# schema.net
KiCad netlist of a schematic drawn in EAGLE
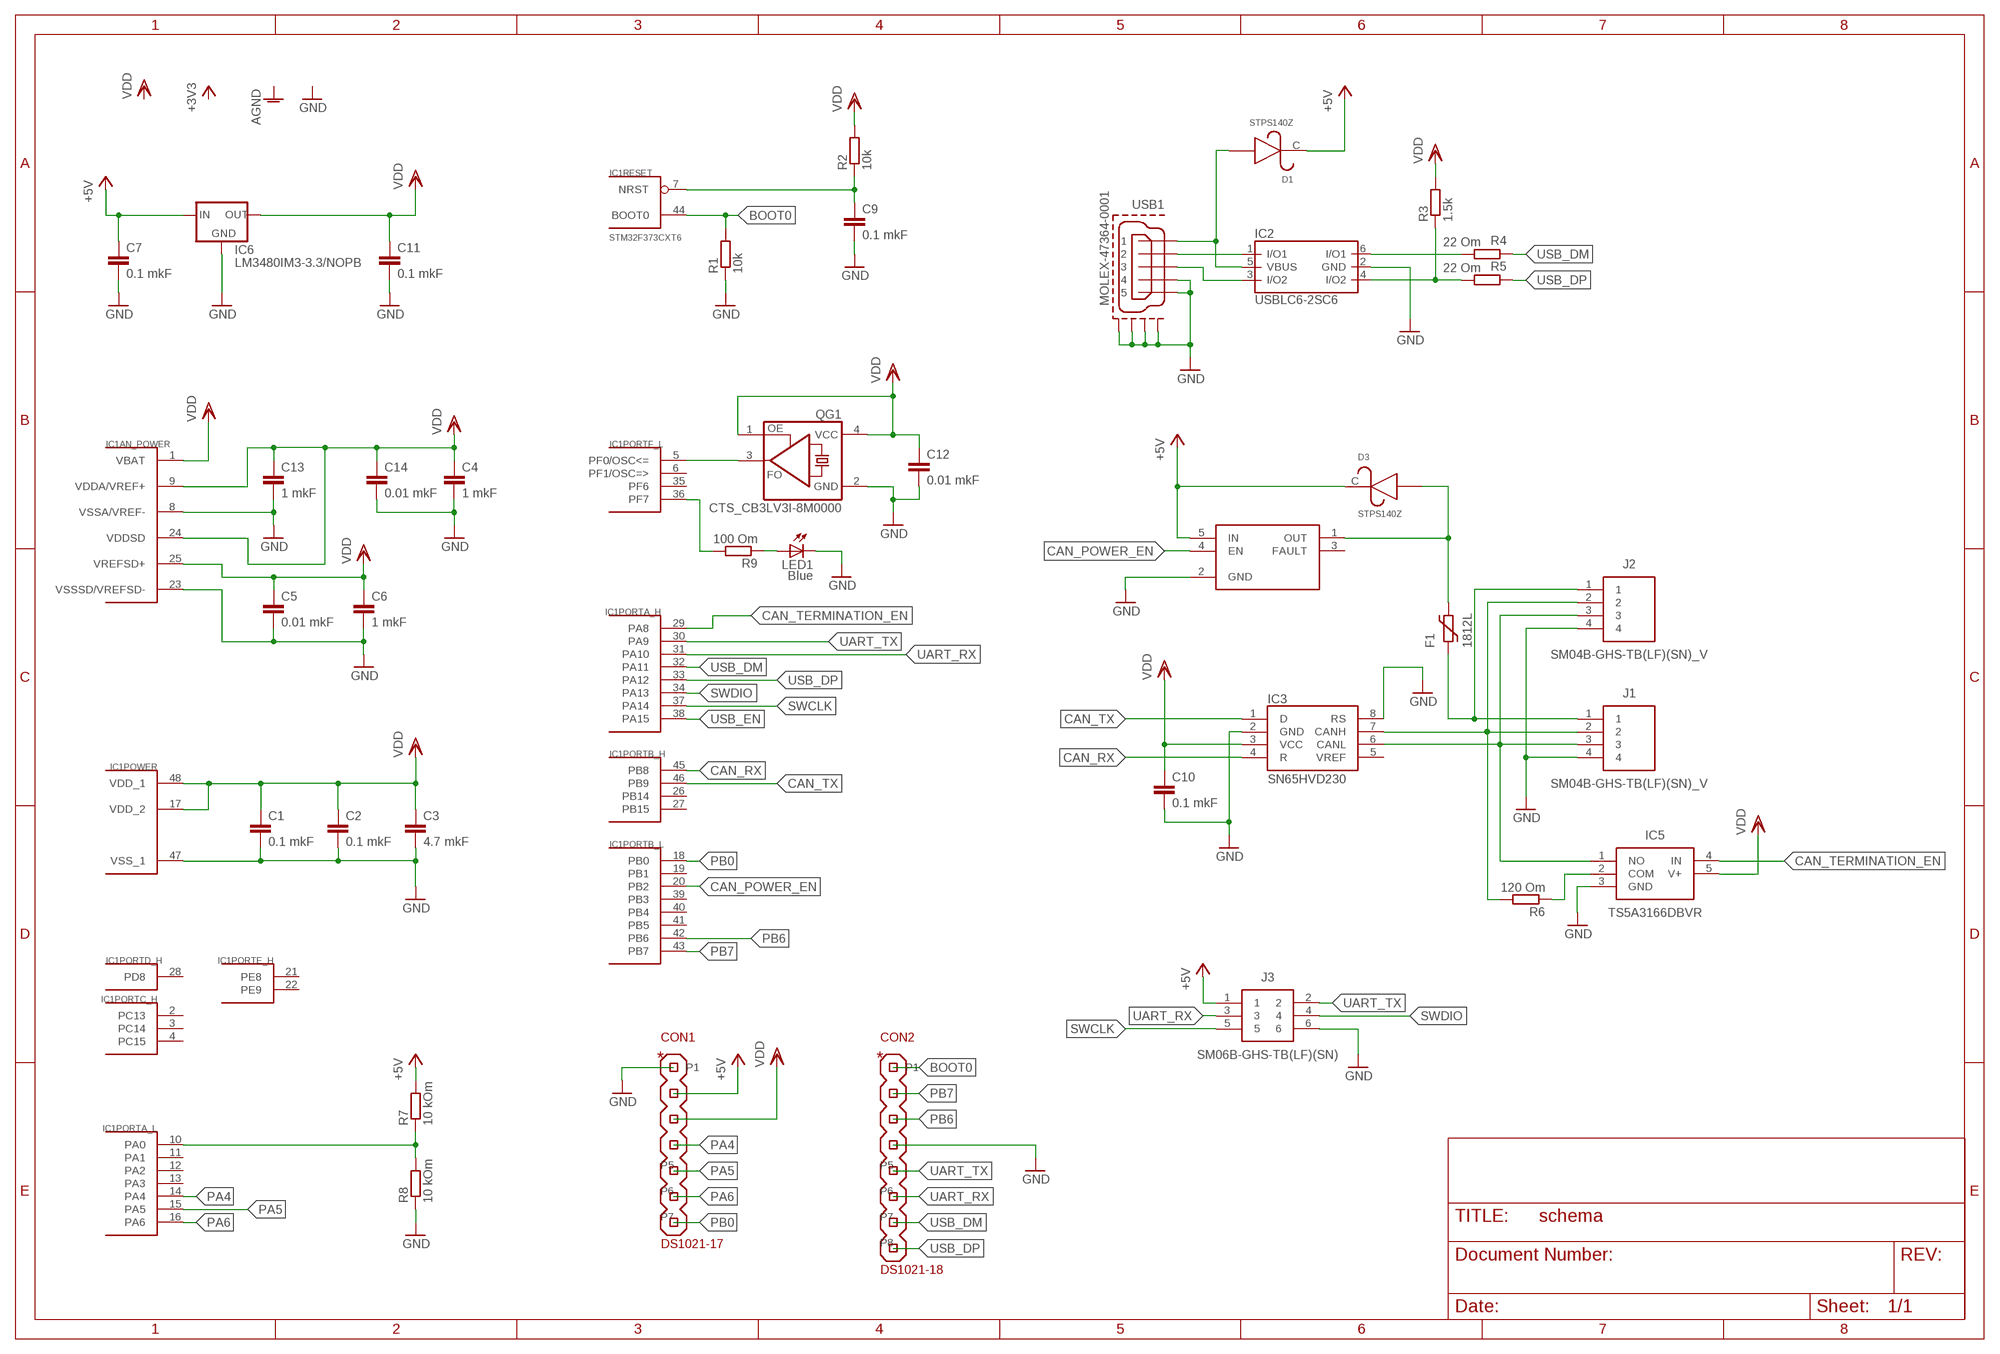
[diagram p0: schematic, sheet 1]

(export (version "E")
  (design (tool "Eeschema 10.0.6"))
  (components
    (comp (ref "C1")
      (value "0.1 mkF")
      (footprint "eagle-import:C0603")
      (libsource (lib "eagle-import") (part "C-EUC0603"))
    )
    (comp (ref "C2")
      (value "0.1 mkF")
      (footprint "eagle-import:C0603")
      (libsource (lib "eagle-import") (part "C-EUC0603"))
    )
    (comp (ref "C3")
      (value "4.7 mkF")
      (footprint "eagle-import:C0805")
      (libsource (lib "eagle-import") (part "C-EUC0805"))
    )
    (comp (ref "C4")
      (value "1 mkF")
      (footprint "eagle-import:C0603")
      (libsource (lib "eagle-import") (part "C-EUC0603"))
    )
    (comp (ref "C5")
      (value "0.01 mkF")
      (footprint "eagle-import:C0603")
      (libsource (lib "eagle-import") (part "C-EUC0603"))
    )
    (comp (ref "C6")
      (value "1 mkF")
      (footprint "eagle-import:C0603")
      (libsource (lib "eagle-import") (part "C-EUC0603"))
    )
    (comp (ref "C7")
      (value "0.1 mkF")
      (footprint "eagle-import:C0603")
      (libsource (lib "eagle-import") (part "C-EUC0603"))
    )
    (comp (ref "C9")
      (value "0.1 mkF")
      (footprint "eagle-import:C0603")
      (libsource (lib "eagle-import") (part "C-EUC0603"))
    )
    (comp (ref "C10")
      (value "0.1 mkF")
      (footprint "eagle-import:C0603")
      (libsource (lib "eagle-import") (part "C-EUC0603"))
    )
    (comp (ref "C11")
      (value "0.1 mkF")
      (footprint "eagle-import:C0603")
      (libsource (lib "eagle-import") (part "C-EUC0603"))
    )
    (comp (ref "C12")
      (value "0.01 mkF")
      (footprint "eagle-import:C0603")
      (libsource (lib "eagle-import") (part "C-EUC0603"))
    )
    (comp (ref "C13")
      (value "1 mkF")
      (footprint "eagle-import:C0603")
      (libsource (lib "eagle-import") (part "C-EUC0603"))
    )
    (comp (ref "C14")
      (value "0.01 mkF")
      (footprint "eagle-import:C0603")
      (libsource (lib "eagle-import") (part "C-EUC0603"))
    )
    (comp (ref "CON1")
      (value "DS1021-17")
      (footprint "eagle-import:DS1021-1_7")
      (libsource (lib "eagle-import") (part "DS1021-17"))
    )
    (comp (ref "CON2")
      (value "DS1021-18")
      (footprint "eagle-import:DS1021-1_8")
      (libsource (lib "eagle-import") (part "DS1021-18"))
    )
    (comp (ref "D1")
      (value "STPS140Z")
      (footprint "eagle-import:SOD123")
      (libsource (lib "eagle-import") (part "STPS140Z"))
    )
    (comp (ref "D3")
      (value "STPS140Z")
      (footprint "eagle-import:SOD123")
      (libsource (lib "eagle-import") (part "STPS140Z"))
    )
    (comp (ref "F1")
      (value "1812L")
      (footprint "eagle-import:1812L")
      (libsource (lib "eagle-import") (part "1812L"))
    )
    (comp (ref "IC1")
      (value "STM32F373CXT6")
      (footprint "eagle-import:TQFP48")
      (libsource (lib "eagle-import") (part "STM32F373CXT6"))
    )
    (comp (ref "IC2")
      (value "USBLC6-2SC6")
      (footprint "eagle-import:SOT23-6L")
      (libsource (lib "eagle-import") (part "USBLC6-2SC6"))
    )
    (comp (ref "IC3")
      (value "SN65HVD230")
      (footprint "eagle-import:SO8")
      (libsource (lib "eagle-import") (part "SN65HVD230"))
    )
    (comp (ref "IC5")
      (value "TS5A3166DBVR")
      (footprint "eagle-import:SOT23-5")
      (libsource (lib "eagle-import") (part "TS5A3166DBVR"))
    )
    (comp (ref "IC6")
      (value "LM3480IM3-3.3/NOPB")
      (footprint "eagle-import:SOT23")
      (libsource (lib "eagle-import") (part "LM3480IM3-3.3/NOPB"))
    )
    (comp (ref "IC7")
      (value "STMPS2171STR")
      (footprint "eagle-import:SOT23-5L")
      (libsource (lib "eagle-import") (part "STMPS2171STR"))
    )
    (comp (ref "J1")
      (value "SM04B-GHS-TB(LF)(SN)_V")
      (footprint "eagle-import:SM04B-GHS-TB")
      (fields
        (field (name "MANUFACTURER_PART_NUMBER") "SM04B-GHS-TB(LF)(SN)")
        (field (name "RS_PART_NUMBER") "7521797")
      )
      (libsource (lib "eagle-import") (part "SM04B-GHS-TB(LF)(SN)_V"))
    )
    (comp (ref "J2")
      (value "SM04B-GHS-TB(LF)(SN)_V")
      (footprint "eagle-import:SM04B-GHS-TB")
      (fields
        (field (name "MANUFACTURER_PART_NUMBER") "SM04B-GHS-TB(LF)(SN)")
        (field (name "RS_PART_NUMBER") "7521797")
      )
      (libsource (lib "eagle-import") (part "SM04B-GHS-TB(LF)(SN)_V"))
    )
    (comp (ref "J3")
      (value "SM06B-GHS-TB(LF)(SN)")
      (footprint "eagle-import:SM06B-GHS-TB")
      (fields (field (name "RS_PART_NUMBER") "7521800"))
      (libsource (lib "eagle-import") (part "SM06B-GHS-TB(LF)(SN)"))
    )
    (comp (ref "LED1")
      (value "Blue")
      (footprint "eagle-import:CHIPLED_0603")
      (libsource (lib "eagle-import") (part "LEDCHIPLED_0603"))
    )
    (comp (ref "QG1")
      (value "CTS_CB3LV3I-8M0000")
      (footprint "eagle-import:CTS_CB3")
      (libsource (lib "eagle-import") (part "CTS_CB3LV3I-8M0000"))
    )
    (comp (ref "R1")
      (value "10k")
      (footprint "eagle-import:R0603")
      (libsource (lib "eagle-import") (part "R-EU_R0603"))
    )
    (comp (ref "R2")
      (value "10k")
      (footprint "eagle-import:R0603")
      (libsource (lib "eagle-import") (part "R-EU_R0603"))
    )
    (comp (ref "R3")
      (value "1.5k")
      (footprint "eagle-import:R0603")
      (libsource (lib "eagle-import") (part "R-EU_R0603"))
    )
    (comp (ref "R4")
      (value "22 Om")
      (footprint "eagle-import:R0603")
      (libsource (lib "eagle-import") (part "R-EU_R0603"))
    )
    (comp (ref "R5")
      (value "22 Om")
      (footprint "eagle-import:R0603")
      (libsource (lib "eagle-import") (part "R-EU_R0603"))
    )
    (comp (ref "R6")
      (value "120 Om")
      (footprint "eagle-import:R1206")
      (libsource (lib "eagle-import") (part "R-EU_R1206"))
    )
    (comp (ref "R7")
      (value "10 kOm")
      (footprint "eagle-import:R0603")
      (libsource (lib "eagle-import") (part "R-EU_R0603"))
    )
    (comp (ref "R8")
      (value "10 kOm")
      (footprint "eagle-import:R0603")
      (libsource (lib "eagle-import") (part "R-EU_R0603"))
    )
    (comp (ref "R9")
      (value "100 Om")
      (footprint "eagle-import:R0603")
      (libsource (lib "eagle-import") (part "R-EU_R0603"))
    )
    (comp (ref "USB1")
      (value "MOLEX-47364-0001")
      (footprint "eagle-import:MOLEX-47364-0001")
      (libsource (lib "eagle-import") (part "MOLEX-47364-0001"))
    )
  )
  (nets
    (net (code "2") (name "+5V") (class "Default")
      (node (ref "C7") (pin "1") (pinfunction "1_1") (pintype "passive"))
      (node (ref "CON1") (pin "P2") (pinfunction "P2_P2") (pintype "bidirectional"))
      (node (ref "D1") (pin "C") (pinfunction "C_C") (pintype "power_in"))
      (node (ref "D3") (pin "C") (pinfunction "C_C") (pintype "power_in"))
      (node (ref "IC6") (pin "2") (pinfunction "IN_2") (pintype "input"))
      (node (ref "IC7") (pin "5") (pinfunction "IN_5") (pintype "power_in"))
      (node (ref "J3") (pin "1") (pinfunction "1_1") (pintype "passive"))
      (node (ref "R7") (pin "2") (pinfunction "2_2") (pintype "passive"))
    )
    (net (code "4") (name "BOOT0") (class "Default")
      (node (ref "CON2") (pin "P1") (pinfunction "P1_P1") (pintype "bidirectional"))
      (node (ref "IC1") (pin "44") (pinfunction "BOOT0_44") (pintype "input"))
      (node (ref "R1") (pin "2") (pinfunction "2_2") (pintype "passive"))
    )
    (net (code "5") (name "CAN_POWER_EN") (class "Default")
      (node (ref "IC1") (pin "20") (pinfunction "PB2_20") (pintype "bidirectional"))
      (node (ref "IC7") (pin "4") (pinfunction "EN_4") (pintype "bidirectional"))
    )
    (net (code "6") (name "CAN_RX") (class "Default")
      (node (ref "IC1") (pin "45") (pinfunction "PB8_45") (pintype "bidirectional"))
      (node (ref "IC3") (pin "4") (pinfunction "R_4") (pintype "bidirectional"))
    )
    (net (code "7") (name "CAN_TERMINATION_EN") (class "Default")
      (node (ref "IC1") (pin "29") (pinfunction "PA8_29") (pintype "bidirectional"))
      (node (ref "IC5") (pin "4") (pinfunction "IN_4") (pintype "passive"))
    )
    (net (code "8") (name "CAN_TX") (class "Default")
      (node (ref "IC1") (pin "46") (pinfunction "PB9_46") (pintype "bidirectional"))
      (node (ref "IC3") (pin "1") (pinfunction "D_1") (pintype "bidirectional"))
    )
    (net (code "9") (name "GND") (class "Default")
      (node (ref "C1") (pin "2") (pinfunction "2_2") (pintype "passive"))
      (node (ref "C10") (pin "2") (pinfunction "2_2") (pintype "passive"))
      (node (ref "C11") (pin "2") (pinfunction "2_2") (pintype "passive"))
      (node (ref "C12") (pin "2") (pinfunction "2_2") (pintype "passive"))
      (node (ref "C13") (pin "2") (pinfunction "2_2") (pintype "passive"))
      (node (ref "C14") (pin "2") (pinfunction "2_2") (pintype "passive"))
      (node (ref "C2") (pin "2") (pinfunction "2_2") (pintype "passive"))
      (node (ref "C3") (pin "2") (pinfunction "2_2") (pintype "passive"))
      (node (ref "C4") (pin "2") (pinfunction "2_2") (pintype "passive"))
      (node (ref "C5") (pin "2") (pinfunction "2_2") (pintype "passive"))
      (node (ref "C6") (pin "2") (pinfunction "2_2") (pintype "passive"))
      (node (ref "C7") (pin "2") (pinfunction "2_2") (pintype "passive"))
      (node (ref "C9") (pin "2") (pinfunction "2_2") (pintype "passive"))
      (node (ref "CON1") (pin "P1") (pinfunction "P1_P1") (pintype "bidirectional"))
      (node (ref "CON2") (pin "P4") (pinfunction "P4_P4") (pintype "bidirectional"))
      (node (ref "IC1") (pin "23") (pinfunction "VSSSD/VREFSD-_23") (pintype "power_in"))
      (node (ref "IC1") (pin "47") (pinfunction "VSS_1_47") (pintype "power_in"))
      (node (ref "IC1") (pin "8") (pinfunction "VSSA/VREF-_8") (pintype "power_in"))
      (node (ref "IC2") (pin "2") (pinfunction "GND_2") (pintype "power_in"))
      (node (ref "IC3") (pin "2") (pinfunction "GND_2") (pintype "power_in"))
      (node (ref "IC3") (pin "8") (pinfunction "RS_8") (pintype "bidirectional"))
      (node (ref "IC5") (pin "3") (pinfunction "GND_3") (pintype "passive"))
      (node (ref "IC6") (pin "3") (pinfunction "GND_3") (pintype "input"))
      (node (ref "IC7") (pin "2") (pinfunction "GND_2") (pintype "power_in"))
      (node (ref "J1") (pin "4") (pinfunction "4_4") (pintype "passive"))
      (node (ref "J2") (pin "4") (pinfunction "4_4") (pintype "passive"))
      (node (ref "J3") (pin "6") (pinfunction "6_6") (pintype "passive"))
      (node (ref "LED1") (pin "C") (pinfunction "C_C") (pintype "passive"))
      (node (ref "QG1") (pin "2") (pinfunction "GND_2") (pintype "power_in"))
      (node (ref "R1") (pin "1") (pinfunction "1_1") (pintype "passive"))
      (node (ref "R8") (pin "1") (pinfunction "1_1") (pintype "passive"))
      (node (ref "USB1") (pin "4") (pinfunction "4_4") (pintype "input"))
      (node (ref "USB1") (pin "5") (pinfunction "5_5") (pintype "input"))
      (node (ref "USB1") (pin "GND1") (pinfunction "GND1_GND1") (pintype "bidirectional"))
      (node (ref "USB1") (pin "GND2") (pinfunction "GND2_GND2") (pintype "bidirectional"))
      (node (ref "USB1") (pin "GND3") (pinfunction "GND3_GND3") (pintype "bidirectional"))
      (node (ref "USB1") (pin "GND4") (pinfunction "GND4_GND4") (pintype "bidirectional"))
    )
    (net (code "10") (name "Net-(F1-Pad1)") (class "Default")
      (node (ref "F1") (pin "1") (pinfunction "1_1") (pintype "passive"))
      (node (ref "J1") (pin "1") (pinfunction "1_1") (pintype "passive"))
      (node (ref "J2") (pin "1") (pinfunction "1_1") (pintype "passive"))
    )
    (net (code "11") (name "Net-(IC1C-PA0)") (class "Default")
      (node (ref "IC1") (pin "10") (pinfunction "PA0_10") (pintype "bidirectional"))
      (node (ref "R7") (pin "1") (pinfunction "1_1") (pintype "passive"))
      (node (ref "R8") (pin "2") (pinfunction "2_2") (pintype "passive"))
    )
    (net (code "12") (name "Net-(IC1I-PF0{slash}OSC<=)") (class "Default")
      (node (ref "IC1") (pin "5") (pinfunction "PF0/OSC<=_5") (pintype "bidirectional"))
      (node (ref "QG1") (pin "3") (pinfunction "FO_3") (pintype "output"))
    )
    (net (code "13") (name "Net-(IC1I-PF7)") (class "Default")
      (node (ref "IC1") (pin "36") (pinfunction "PF7_36") (pintype "bidirectional"))
      (node (ref "R9") (pin "2") (pinfunction "2_2") (pintype "passive"))
    )
    (net (code "14") (name "Net-(IC1K-NRST)") (class "Default")
      (node (ref "C9") (pin "1") (pinfunction "1_1") (pintype "passive"))
      (node (ref "IC1") (pin "7") (pinfunction "NRST_7") (pintype "input"))
      (node (ref "R2") (pin "1") (pinfunction "1_1") (pintype "passive"))
    )
    (net (code "15") (name "Net-(IC2-I{slash}O1-Pad1)") (class "Default")
      (node (ref "IC2") (pin "1") (pinfunction "I/O1_1") (pintype "bidirectional"))
      (node (ref "USB1") (pin "2") (pinfunction "2_2") (pintype "input"))
    )
    (net (code "16") (name "Net-(IC2-I{slash}O1-Pad6)") (class "Default")
      (node (ref "IC2") (pin "6") (pinfunction "I/O1_6") (pintype "bidirectional"))
      (node (ref "R4") (pin "2") (pinfunction "2_2") (pintype "passive"))
    )
    (net (code "17") (name "Net-(IC2-I{slash}O2-Pad3)") (class "Default")
      (node (ref "IC2") (pin "3") (pinfunction "I/O2_3") (pintype "bidirectional"))
      (node (ref "USB1") (pin "3") (pinfunction "3_3") (pintype "input"))
    )
    (net (code "18") (name "Net-(IC2-I{slash}O2-Pad4)") (class "Default")
      (node (ref "IC2") (pin "4") (pinfunction "I/O2_4") (pintype "bidirectional"))
      (node (ref "R3") (pin "1") (pinfunction "1_1") (pintype "passive"))
      (node (ref "R5") (pin "2") (pinfunction "2_2") (pintype "passive"))
    )
    (net (code "19") (name "Net-(IC2-VBUS)") (class "Default")
      (node (ref "D1") (pin "A") (pinfunction "A_A") (pintype "power_in"))
      (node (ref "IC2") (pin "5") (pinfunction "VBUS_5") (pintype "power_in"))
      (node (ref "USB1") (pin "1") (pinfunction "1_1") (pintype "input"))
    )
    (net (code "20") (name "Net-(IC3-CANH)") (class "Default")
      (node (ref "IC3") (pin "7") (pinfunction "CANH_7") (pintype "bidirectional"))
      (node (ref "J1") (pin "2") (pinfunction "2_2") (pintype "passive"))
      (node (ref "J2") (pin "2") (pinfunction "2_2") (pintype "passive"))
      (node (ref "R6") (pin "2") (pinfunction "2_2") (pintype "passive"))
    )
    (net (code "21") (name "Net-(IC3-CANL)") (class "Default")
      (node (ref "IC3") (pin "6") (pinfunction "CANL_6") (pintype "bidirectional"))
      (node (ref "IC5") (pin "1") (pinfunction "NO_1") (pintype "passive"))
      (node (ref "J1") (pin "3") (pinfunction "3_3") (pintype "passive"))
      (node (ref "J2") (pin "3") (pinfunction "3_3") (pintype "passive"))
    )
    (net (code "22") (name "Net-(IC5-COM)") (class "Default")
      (node (ref "IC5") (pin "2") (pinfunction "COM_2") (pintype "passive"))
      (node (ref "R6") (pin "1") (pinfunction "1_1") (pintype "passive"))
    )
    (net (code "23") (name "Net-(IC7-OUT)") (class "Default")
      (node (ref "D3") (pin "A") (pinfunction "A_A") (pintype "power_in"))
      (node (ref "F1") (pin "2") (pinfunction "2_2") (pintype "passive"))
      (node (ref "IC7") (pin "1") (pinfunction "OUT_1") (pintype "power_in"))
    )
    (net (code "24") (name "Net-(LED1-PadA)") (class "Default")
      (node (ref "LED1") (pin "A") (pinfunction "A_A") (pintype "passive"))
      (node (ref "R9") (pin "1") (pinfunction "1_1") (pintype "passive"))
    )
    (net (code "25") (name "PA4") (class "Default")
      (node (ref "CON1") (pin "P4") (pinfunction "P4_P4") (pintype "bidirectional"))
      (node (ref "IC1") (pin "14") (pinfunction "PA4_14") (pintype "bidirectional"))
    )
    (net (code "26") (name "PA5") (class "Default")
      (node (ref "CON1") (pin "P5") (pinfunction "P5_P5") (pintype "bidirectional"))
      (node (ref "IC1") (pin "15") (pinfunction "PA5_15") (pintype "bidirectional"))
    )
    (net (code "27") (name "PA6") (class "Default")
      (node (ref "CON1") (pin "P6") (pinfunction "P6_P6") (pintype "bidirectional"))
      (node (ref "IC1") (pin "16") (pinfunction "PA6_16") (pintype "bidirectional"))
    )
    (net (code "28") (name "PB0") (class "Default")
      (node (ref "CON1") (pin "P7") (pinfunction "P7_P7") (pintype "bidirectional"))
      (node (ref "IC1") (pin "18") (pinfunction "PB0_18") (pintype "bidirectional"))
    )
    (net (code "29") (name "PB6") (class "Default")
      (node (ref "CON2") (pin "P3") (pinfunction "P3_P3") (pintype "bidirectional"))
      (node (ref "IC1") (pin "42") (pinfunction "PB6_42") (pintype "bidirectional"))
    )
    (net (code "30") (name "PB7") (class "Default")
      (node (ref "CON2") (pin "P2") (pinfunction "P2_P2") (pintype "bidirectional"))
      (node (ref "IC1") (pin "43") (pinfunction "PB7_43") (pintype "bidirectional"))
    )
    (net (code "31") (name "SWCLK") (class "Default")
      (node (ref "IC1") (pin "37") (pinfunction "PA14_37") (pintype "bidirectional"))
      (node (ref "J3") (pin "5") (pinfunction "5_5") (pintype "passive"))
    )
    (net (code "32") (name "SWDIO") (class "Default")
      (node (ref "IC1") (pin "34") (pinfunction "PA13_34") (pintype "bidirectional"))
      (node (ref "J3") (pin "4") (pinfunction "4_4") (pintype "passive"))
    )
    (net (code "33") (name "UART_RX") (class "Default")
      (node (ref "CON2") (pin "P6") (pinfunction "P6_P6") (pintype "bidirectional"))
      (node (ref "IC1") (pin "31") (pinfunction "PA10_31") (pintype "bidirectional"))
      (node (ref "J3") (pin "3") (pinfunction "3_3") (pintype "passive"))
    )
    (net (code "34") (name "UART_TX") (class "Default")
      (node (ref "CON2") (pin "P5") (pinfunction "P5_P5") (pintype "bidirectional"))
      (node (ref "IC1") (pin "30") (pinfunction "PA9_30") (pintype "bidirectional"))
      (node (ref "J3") (pin "2") (pinfunction "2_2") (pintype "passive"))
    )
    (net (code "35") (name "USB_DM") (class "Default")
      (node (ref "CON2") (pin "P7") (pinfunction "P7_P7") (pintype "bidirectional"))
      (node (ref "IC1") (pin "32") (pinfunction "PA11_32") (pintype "bidirectional"))
      (node (ref "R4") (pin "1") (pinfunction "1_1") (pintype "passive"))
    )
    (net (code "36") (name "USB_DP") (class "Default")
      (node (ref "CON2") (pin "P8") (pinfunction "P8_P8") (pintype "bidirectional"))
      (node (ref "IC1") (pin "33") (pinfunction "PA12_33") (pintype "bidirectional"))
      (node (ref "R5") (pin "1") (pinfunction "1_1") (pintype "passive"))
    )
    (net (code "37") (name "USB_EN") (class "Default")
      (node (ref "IC1") (pin "38") (pinfunction "PA15_38") (pintype "bidirectional"))
    )
    (net (code "38") (name "VDD") (class "Default")
      (node (ref "C1") (pin "1") (pinfunction "1_1") (pintype "passive"))
      (node (ref "C10") (pin "1") (pinfunction "1_1") (pintype "passive"))
      (node (ref "C11") (pin "1") (pinfunction "1_1") (pintype "passive"))
      (node (ref "C12") (pin "1") (pinfunction "1_1") (pintype "passive"))
      (node (ref "C13") (pin "1") (pinfunction "1_1") (pintype "passive"))
      (node (ref "C14") (pin "1") (pinfunction "1_1") (pintype "passive"))
      (node (ref "C2") (pin "1") (pinfunction "1_1") (pintype "passive"))
      (node (ref "C3") (pin "1") (pinfunction "1_1") (pintype "passive"))
      (node (ref "C4") (pin "1") (pinfunction "1_1") (pintype "passive"))
      (node (ref "C5") (pin "1") (pinfunction "1_1") (pintype "passive"))
      (node (ref "C6") (pin "1") (pinfunction "1_1") (pintype "passive"))
      (node (ref "CON1") (pin "P3") (pinfunction "P3_P3") (pintype "bidirectional"))
      (node (ref "IC1") (pin "1") (pinfunction "VBAT_1") (pintype "power_in"))
      (node (ref "IC1") (pin "17") (pinfunction "VDD_2_17") (pintype "power_in"))
      (node (ref "IC1") (pin "24") (pinfunction "VDDSD_24") (pintype "power_in"))
      (node (ref "IC1") (pin "25") (pinfunction "VREFSD+_25") (pintype "power_in"))
      (node (ref "IC1") (pin "48") (pinfunction "VDD_1_48") (pintype "power_in"))
      (node (ref "IC1") (pin "9") (pinfunction "VDDA/VREF+_9") (pintype "power_in"))
      (node (ref "IC3") (pin "3") (pinfunction "VCC_3") (pintype "power_in"))
      (node (ref "IC5") (pin "5") (pinfunction "V+_5") (pintype "passive"))
      (node (ref "IC6") (pin "1") (pinfunction "OUT_1") (pintype "passive"))
      (node (ref "QG1") (pin "1") (pinfunction "OE_1") (pintype "input"))
      (node (ref "QG1") (pin "4") (pinfunction "VCC_4") (pintype "power_in"))
      (node (ref "R2") (pin "2") (pinfunction "2_2") (pintype "passive"))
      (node (ref "R3") (pin "2") (pinfunction "2_2") (pintype "passive"))
    )
    (net (code "39") (name "unconnected-(IC1C-PA1-Pad11)") (class "Default")
      (node (ref "IC1") (pin "11") (pinfunction "PA1_11") (pintype "bidirectional"))
    )
    (net (code "40") (name "unconnected-(IC1C-PA2-Pad12)") (class "Default")
      (node (ref "IC1") (pin "12") (pinfunction "PA2_12") (pintype "bidirectional"))
    )
    (net (code "41") (name "unconnected-(IC1C-PA3-Pad13)") (class "Default")
      (node (ref "IC1") (pin "13") (pinfunction "PA3_13") (pintype "bidirectional"))
    )
    (net (code "42") (name "unconnected-(IC1D-PB14-Pad26)") (class "Default")
      (node (ref "IC1") (pin "26") (pinfunction "PB14_26") (pintype "bidirectional"))
    )
    (net (code "43") (name "unconnected-(IC1D-PB15-Pad27)") (class "Default")
      (node (ref "IC1") (pin "27") (pinfunction "PB15_27") (pintype "bidirectional"))
    )
    (net (code "44") (name "unconnected-(IC1E-PB1-Pad19)") (class "Default")
      (node (ref "IC1") (pin "19") (pinfunction "PB1_19") (pintype "bidirectional"))
    )
    (net (code "45") (name "unconnected-(IC1E-PB3-Pad39)") (class "Default")
      (node (ref "IC1") (pin "39") (pinfunction "PB3_39") (pintype "bidirectional"))
    )
    (net (code "46") (name "unconnected-(IC1E-PB4-Pad40)") (class "Default")
      (node (ref "IC1") (pin "40") (pinfunction "PB4_40") (pintype "bidirectional"))
    )
    (net (code "47") (name "unconnected-(IC1E-PB5-Pad41)") (class "Default")
      (node (ref "IC1") (pin "41") (pinfunction "PB5_41") (pintype "bidirectional"))
    )
    (net (code "48") (name "unconnected-(IC1F-PC13-Pad2)") (class "Default")
      (node (ref "IC1") (pin "2") (pinfunction "PC13_2") (pintype "bidirectional"))
    )
    (net (code "49") (name "unconnected-(IC1F-PC14-Pad3)") (class "Default")
      (node (ref "IC1") (pin "3") (pinfunction "PC14_3") (pintype "bidirectional"))
    )
    (net (code "50") (name "unconnected-(IC1F-PC15-Pad4)") (class "Default")
      (node (ref "IC1") (pin "4") (pinfunction "PC15_4") (pintype "bidirectional"))
    )
    (net (code "51") (name "unconnected-(IC1G-PD8-Pad28)") (class "Default")
      (node (ref "IC1") (pin "28") (pinfunction "PD8_28") (pintype "bidirectional"))
    )
    (net (code "52") (name "unconnected-(IC1H-PE8-Pad21)") (class "Default")
      (node (ref "IC1") (pin "21") (pinfunction "PE8_21") (pintype "bidirectional"))
    )
    (net (code "53") (name "unconnected-(IC1H-PE9-Pad22)") (class "Default")
      (node (ref "IC1") (pin "22") (pinfunction "PE9_22") (pintype "bidirectional"))
    )
    (net (code "54") (name "unconnected-(IC1I-PF1{slash}OSC=>-Pad6)") (class "Default")
      (node (ref "IC1") (pin "6") (pinfunction "PF1/OSC=>_6") (pintype "bidirectional"))
    )
    (net (code "55") (name "unconnected-(IC1I-PF6-Pad35)") (class "Default")
      (node (ref "IC1") (pin "35") (pinfunction "PF6_35") (pintype "bidirectional"))
    )
    (net (code "56") (name "unconnected-(IC3-VREF-Pad5)") (class "Default")
      (node (ref "IC3") (pin "5") (pinfunction "VREF_5") (pintype "bidirectional"))
    )
    (net (code "57") (name "unconnected-(IC7-FAULT-Pad3)") (class "Default")
      (node (ref "IC7") (pin "3") (pinfunction "FAULT_3") (pintype "bidirectional"))
    )
  )
)
